# 07_-SDcard_Testpoints_Ext_SPI_Interface.net
KiCad netlist of a schematic drawn in Altium Designer
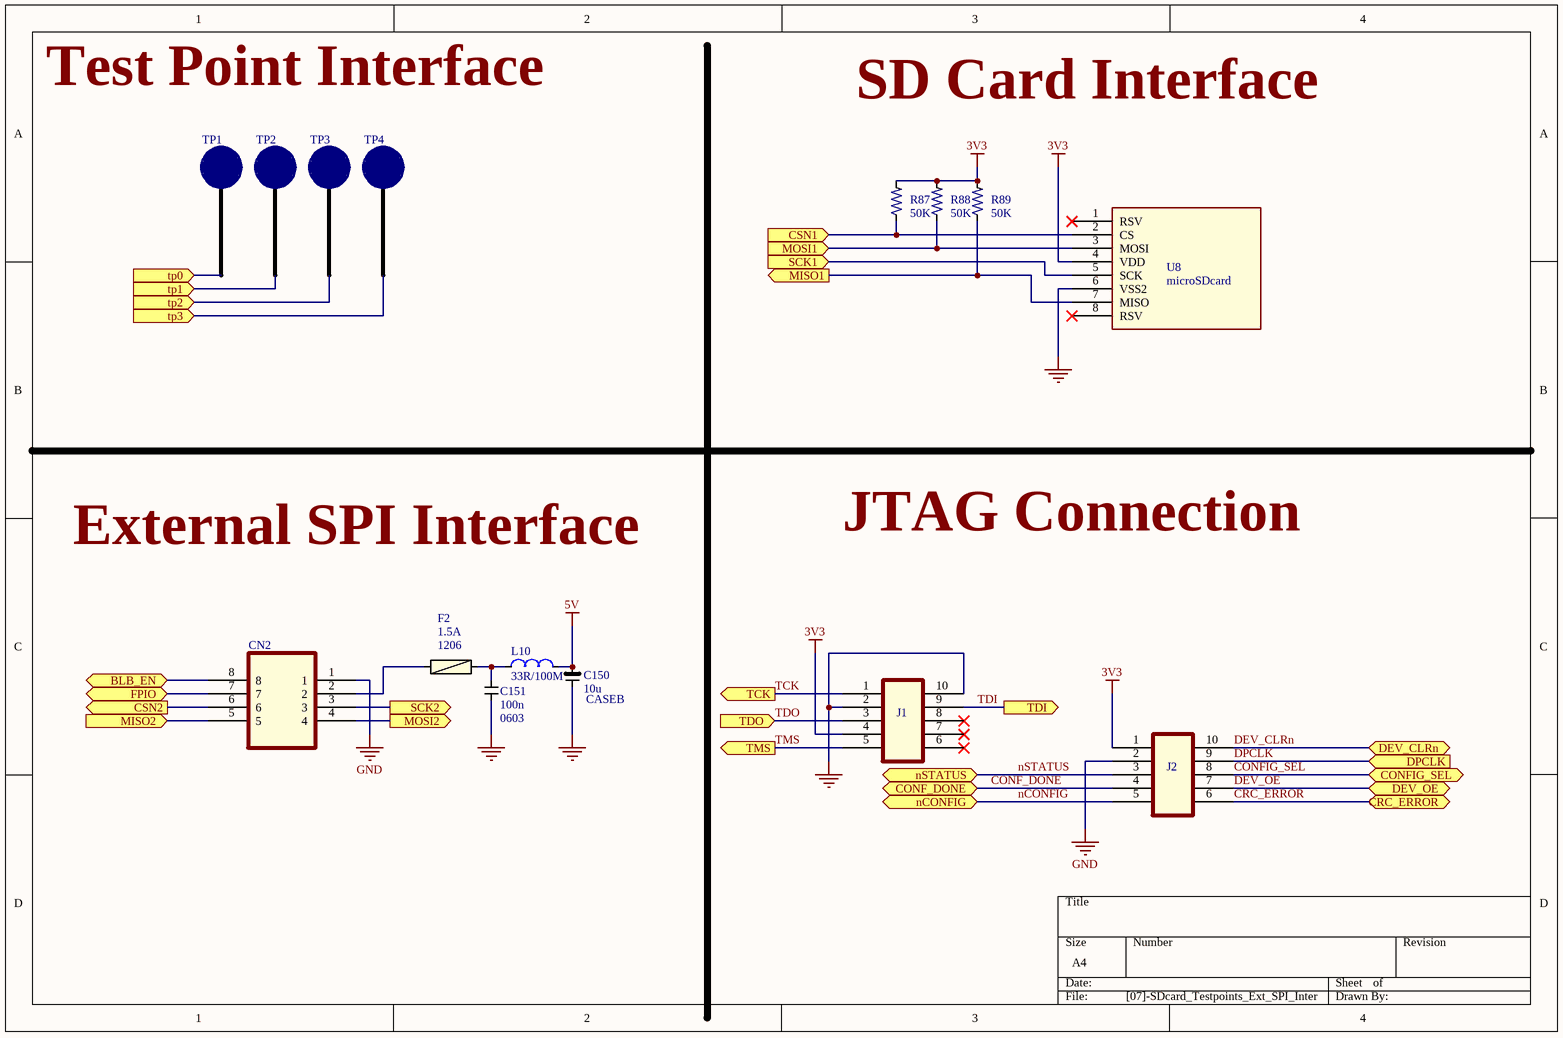
[diagram p0: [07]-SDcard_Testpoints_Ext_SPI_Interface.SchDoc]

(export (version "E")
  (design (tool "Eeschema 10.0.6"))
  (components
    (comp (ref "C150")
      (value "10u")
      (footprint "CAPC3528X21N")
      (fields (field (name "PCB LAYER") "CASEB"))
      (libsource (lib "T495B106K010ATE600") (part "Component_1"))
    )
    (comp (ref "C151")
      (value "100n")
      (fields (field (name "PCB FOOTPRINT") "0603"))
      (libsource (lib "06031C104KAT2A") (part "Component_1"))
    )
    (comp (ref "CN2")
      (value "SPI_connector")
      (footprint "TE_7-215079-8_0")
      (description "CONN FMALE-ON-BRD 8POS VERT T/H")
      (libsource (lib "7-215079-8") (part "Conn_TE_7-215079-8_eec"))
    )
    (comp (ref "F2")
      (value "1.5A")
      (footprint "*CAP3216X125N")
      (fields (field (name "PCB TYPE") "1206"))
      (libsource (lib "BLM31PG601SN1L") (part "Component_1"))
    )
    (comp (ref "J1")
      (value "1761681-3")
      (footprint "Harwin_Inc._M50-3500542_0")
      (description "IDC LOW PRO HDR 10P VERT HT BLACK")
      (fields (field (name "MF") "hARWIN") (field (name "MP") "M50-3500542"))
      (libsource (lib "JTAG") (part "1761681-3"))
    )
    (comp (ref "J2")
      (value "1761681-3")
      (footprint "Harwin_Inc._M50-3500542_0")
      (description "IDC LOW PRO HDR 10P VERT HT BLACK")
      (fields (field (name "MF") "hARWIN") (field (name "MP") "M50-3500542"))
      (libsource (lib "JTAG") (part "1761681-3"))
    )
    (comp (ref "L10")
      (value "33R/100M")
      (footprint "*FB_BLM18PG121SN1D")
      (libsource (lib "BLM18PG330SN1D") (part "Component_1"))
    )
    (comp (ref "R87")
      (value "50K")
      (footprint "*RESC1608X60N")
      (description "Res Thin Film 0603 76.8 Ohm 0.1% 1/10W Â±15ppm/Â°C Molded SMD Paper T/R")
      (fields (field (name "MP") "RP73D1J76R8BTDG") (field (name "MF") "TE Connectivity / Holsworthy"))
      (libsource (lib "CRCW0603200KFKEA") (part "RP73D1J76R8BTDG"))
    )
    (comp (ref "R88")
      (value "50K")
      (footprint "*RESC1608X60N")
      (description "Res Thin Film 0603 76.8 Ohm 0.1% 1/10W Â±15ppm/Â°C Molded SMD Paper T/R")
      (fields (field (name "MP") "RP73D1J76R8BTDG") (field (name "MF") "TE Connectivity / Holsworthy"))
      (libsource (lib "CRCW0603200KFKEA") (part "RP73D1J76R8BTDG"))
    )
    (comp (ref "R89")
      (value "50K")
      (footprint "*RESC1608X60N")
      (description "Res Thin Film 0603 76.8 Ohm 0.1% 1/10W Â±15ppm/Â°C Molded SMD Paper T/R")
      (fields (field (name "MP") "RP73D1J76R8BTDG") (field (name "MF") "TE Connectivity / Holsworthy"))
      (libsource (lib "CRCW0603200KFKEA") (part "RP73D1J76R8BTDG"))
    )
    (comp (ref "TP1")
      (value "TEST-7CN")
      (footprint "PCBComponent_1")
      (libsource (lib "TEST-7CN") (part "Component_1"))
    )
    (comp (ref "TP2")
      (value "TEST-7CN")
      (footprint "PCBComponent_1")
      (libsource (lib "TEST-7CN") (part "Component_1"))
    )
    (comp (ref "TP3")
      (value "TEST-7CN")
      (footprint "PCBComponent_1")
      (libsource (lib "TEST-7CN") (part "Component_1"))
    )
    (comp (ref "TP4")
      (value "TEST-7CN")
      (footprint "PCBComponent_1")
      (libsource (lib "TEST-7CN") (part "Component_1"))
    )
    (comp (ref "U8")
      (value "microSDcard")
      (footprint "*MOLEX_500901-0801_500901-0801(Primary)")
      (description "Conn.; IC Socket; Memory Card; 1.10mm Pitch; TransFlash; Hinge Type; Round Corner Top")
      (fields (field (name "MF") "Molex") (field (name "MP") "500901-0801"))
      (libsource (lib "500901-0801") (part "500901-0801"))
    )
  )
  (nets
    (net (code "1") (name "/BLB_EN") (class "Default")
      (node (ref "CN2") (pin "8") (pinfunction "8_8") (pintype "passive"))
    )
    (net (code "2") (name "/CONFIG_SEL") (class "Default") (node (ref "J2") (pin "8") (pintype "passive")))
    (net (code "3") (name "/CONF_DONE") (class "Default") (node (ref "J2") (pin "4") (pintype "passive")))
    (net (code "4") (name "/CRC_ERROR") (class "Default") (node (ref "J2") (pin "6") (pintype "passive")))
    (net (code "5") (name "/CSN1") (class "Default")
      (node (ref "R87") (pin "1") (pinfunction "1_1") (pintype "passive"))
      (node (ref "U8") (pin "2") (pinfunction "CS_2") (pintype "passive"))
    )
    (net (code "6") (name "/CSN2") (class "Default")
      (node (ref "CN2") (pin "6") (pinfunction "6_6") (pintype "passive"))
    )
    (net (code "7") (name "/DEV_CLRn") (class "Default") (node (ref "J2") (pin "10") (pintype "passive")))
    (net (code "8") (name "/DEV_OE") (class "Default") (node (ref "J2") (pin "7") (pintype "passive")))
    (net (code "9") (name "/DPCLK") (class "Default") (node (ref "J2") (pin "9") (pintype "passive")))
    (net (code "10") (name "/FPIO") (class "Default")
      (node (ref "CN2") (pin "7") (pinfunction "7_7") (pintype "passive"))
    )
    (net (code "11") (name "/MISO1") (class "Default")
      (node (ref "R89") (pin "1") (pinfunction "1_1") (pintype "passive"))
      (node (ref "U8") (pin "7") (pinfunction "MISO_7") (pintype "passive"))
    )
    (net (code "12") (name "/MISO2") (class "Default")
      (node (ref "CN2") (pin "5") (pinfunction "5_5") (pintype "passive"))
    )
    (net (code "13") (name "/MOSI1") (class "Default")
      (node (ref "R88") (pin "1") (pinfunction "1_1") (pintype "passive"))
      (node (ref "U8") (pin "3") (pinfunction "MOSI_3") (pintype "passive"))
    )
    (net (code "14") (name "/MOSI2") (class "Default")
      (node (ref "CN2") (pin "4") (pinfunction "4_4") (pintype "passive"))
    )
    (net (code "15") (name "/SCK1") (class "Default")
      (node (ref "U8") (pin "5") (pinfunction "SCK_5") (pintype "passive"))
    )
    (net (code "16") (name "/SCK2") (class "Default")
      (node (ref "CN2") (pin "3") (pinfunction "3_3") (pintype "passive"))
    )
    (net (code "17") (name "/TCK") (class "Default") (node (ref "J1") (pin "1") (pintype "passive")))
    (net (code "18") (name "/TDI") (class "Default") (node (ref "J1") (pin "9") (pintype "passive")))
    (net (code "19") (name "/TDO") (class "Default") (node (ref "J1") (pin "3") (pintype "passive")))
    (net (code "20") (name "/TMS") (class "Default") (node (ref "J1") (pin "5") (pintype "passive")))
    (net (code "21") (name "/nCONFIG") (class "Default") (node (ref "J2") (pin "5") (pintype "passive")))
    (net (code "22") (name "/nSTATUS") (class "Default") (node (ref "J2") (pin "3") (pintype "passive")))
    (net (code "23") (name "/tp0") (class "Default")
      (node (ref "TP1") (pin "1") (pinfunction "1_1") (pintype "passive"))
    )
    (net (code "24") (name "/tp1") (class "Default")
      (node (ref "TP2") (pin "1") (pinfunction "1_1") (pintype "passive"))
    )
    (net (code "25") (name "/tp2") (class "Default")
      (node (ref "TP3") (pin "1") (pinfunction "1_1") (pintype "passive"))
    )
    (net (code "26") (name "/tp3") (class "Default")
      (node (ref "TP4") (pin "1") (pinfunction "1_1") (pintype "passive"))
    )
    (net (code "27") (name "3V3") (class "Default")
      (node (ref "J1") (pin "4") (pintype "passive"))
      (node (ref "J2") (pin "1") (pintype "passive"))
      (node (ref "R87") (pin "2") (pinfunction "2_2") (pintype "passive"))
      (node (ref "R88") (pin "2") (pinfunction "2_2") (pintype "passive"))
      (node (ref "R89") (pin "2") (pinfunction "2_2") (pintype "passive"))
      (node (ref "U8") (pin "4") (pinfunction "VDD_4") (pintype "power_in"))
    )
    (net (code "28") (name "5V") (class "Default")
      (node (ref "C150") (pin "1") (pinfunction "1_1") (pintype "passive"))
      (node (ref "L10") (pin "2") (pinfunction "2_2") (pintype "passive"))
    )
    (net (code "29") (name "GND") (class "Default")
      (node (ref "C150") (pin "2") (pinfunction "2_2") (pintype "passive"))
      (node (ref "C151") (pin "1") (pinfunction "1_1") (pintype "passive"))
      (node (ref "CN2") (pin "1") (pinfunction "1_1") (pintype "passive"))
      (node (ref "J1") (pin "10") (pintype "passive"))
      (node (ref "J1") (pin "2") (pintype "passive"))
      (node (ref "J2") (pin "2") (pintype "passive"))
      (node (ref "U8") (pin "6") (pinfunction "VSS2_6") (pintype "power_in"))
    )
    (net (code "30") (name "Net-(C151-Pad2)") (class "Default")
      (node (ref "C151") (pin "2") (pinfunction "2_2") (pintype "passive"))
      (node (ref "L10") (pin "1") (pinfunction "1_1") (pintype "passive"))
    )
    (net (code "31") (name "Net-(CN2-Pad2)") (class "Default")
      (node (ref "CN2") (pin "2") (pinfunction "2_2") (pintype "passive"))
      (node (ref "F2") (pin "1") (pinfunction "1_1") (pintype "passive"))
    )
    (net (code "32") (name "unconnected-(F2-Pad2)") (class "Default")
      (node (ref "F2") (pin "2") (pinfunction "2_2") (pintype "passive"))
    )
    (net (code "33") (name "unconnected-(J1-Pad6)") (class "Default")
      (node (ref "J1") (pin "6") (pintype "passive+no_connect"))
    )
    (net (code "34") (name "unconnected-(J1-Pad7)") (class "Default")
      (node (ref "J1") (pin "7") (pintype "passive+no_connect"))
    )
    (net (code "35") (name "unconnected-(J1-Pad8)") (class "Default")
      (node (ref "J1") (pin "8") (pintype "passive+no_connect"))
    )
    (net (code "36") (name "unconnected-(U8-RSV-Pad1)") (class "Default")
      (node (ref "U8") (pin "1") (pinfunction "RSV_1") (pintype "open_emitter+no_connect"))
    )
    (net (code "37") (name "unconnected-(U8-RSV-Pad8)") (class "Default")
      (node (ref "U8") (pin "8") (pinfunction "RSV_8") (pintype "open_emitter+no_connect"))
    )
  )
)
